# Motor_Driver.net
KiCad netlist of a schematic drawn in Altium Designer
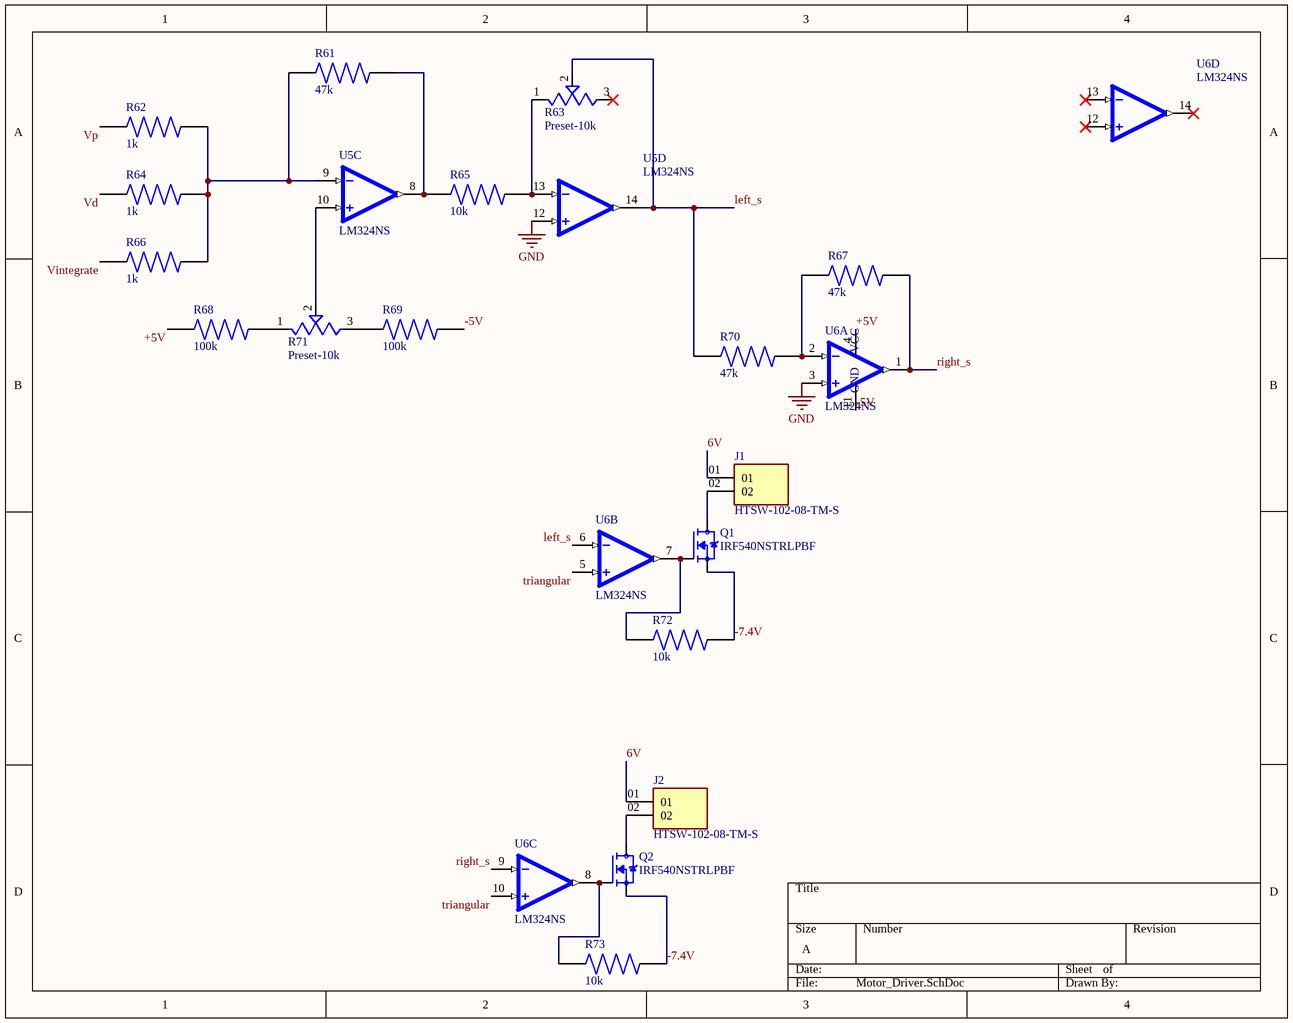
[diagram p0: Motor_Driver.SchDoc]

(export (version "E")
  (design (tool "Eeschema 10.0.6"))
  (components
    (comp (ref "J1")
      (value "HTSW-102-08-TM-S")
      (footprint "SAMTEC_HTSW-102-08-TM-S")
      (fields (field (name "MP") "HTSW10208TMS") (field (name "MF") "Samtec"))
      (libsource (lib "2 pin connector-2") (part "HTSW-102-08-TM-S"))
    )
    (comp (ref "J2")
      (value "HTSW-102-08-TM-S")
      (footprint "SAMTEC_HTSW-102-08-TM-S")
      (fields (field (name "MP") "HTSW10208TMS") (field (name "MF") "Samtec"))
      (libsource (lib "2 pin connector-2") (part "HTSW-102-08-TM-S"))
    )
    (comp (ref "Q1")
      (value "IRF540NSTRLPBF")
      (footprint "TRANS_IRF540NSTRLPBF")
      (fields (field (name "MF") "Infineon"))
      (libsource (lib "mosfet 2") (part "IRF540NSTRLPBF"))
    )
    (comp (ref "Q2")
      (value "IRF540NSTRLPBF")
      (footprint "TRANS_IRF540NSTRLPBF")
      (fields (field (name "MF") "Infineon"))
      (libsource (lib "mosfet 2") (part "IRF540NSTRLPBF"))
    )
    (comp (ref "R61")
      (value "47k")
      (footprint "RESC2012X60N")
      (fields (field (name "MF") "Yageo") (field (name "MP") "RC0805FR-0747KL"))
      (libsource (lib "47ks") (part "47k"))
    )
    (comp (ref "R62")
      (value "1k")
      (footprint "RESC2012X60N")
      (fields
        (field (name "DIGIKEY_PART_NUMBER") "311-1.00KCRTR-ND")
        (field (name "MF") "Yageo")
        (field (name "MP") "RC0805FR-071KL")
      )
      (libsource (lib "1ks") (part "1k"))
    )
    (comp (ref "R63")
      (value "Preset-10k")
      (footprint "TRIM_3306F-1-103")
      (description "TRIMMER - 6MM ROUND, SINGLE-TURN,CERMET, 10K OHMS ¦ Bourns 3306F-1-103")
      (fields (field (name "MF") "Bourns") (field (name "MP") "3306F-1-103"))
      (libsource (lib "3306F-1-103") (part "Preset"))
    )
    (comp (ref "R64")
      (value "1k")
      (footprint "RESC2012X60N")
      (fields
        (field (name "DIGIKEY_PART_NUMBER") "311-1.00KCRTR-ND")
        (field (name "MF") "Yageo")
        (field (name "MP") "RC0805FR-071KL")
      )
      (libsource (lib "1ks") (part "1k"))
    )
    (comp (ref "R65")
      (value "10k")
      (footprint "RESC2012X60N")
      (fields (field (name "MF") "Yageo") (field (name "MP") "RC0805FR-0710KL"))
      (libsource (lib "10ks") (part "10k"))
    )
    (comp (ref "R66")
      (value "1k")
      (footprint "RESC2012X60N")
      (fields
        (field (name "DIGIKEY_PART_NUMBER") "311-1.00KCRTR-ND")
        (field (name "MF") "Yageo")
        (field (name "MP") "RC0805FR-071KL")
      )
      (libsource (lib "1ks") (part "1k"))
    )
    (comp (ref "R67")
      (value "47k")
      (footprint "RESC2012X60N")
      (fields (field (name "MF") "Yageo") (field (name "MP") "RC0805FR-0747KL"))
      (libsource (lib "47ks") (part "47k"))
    )
    (comp (ref "R68")
      (value "100k")
      (footprint "RESC2012X60N")
      (fields (field (name "MF") "Yageo") (field (name "MP") "RC0805FR-07100KL"))
      (libsource (lib "100ks") (part "100k"))
    )
    (comp (ref "R69")
      (value "100k")
      (footprint "RESC2012X60N")
      (fields (field (name "MF") "Yageo") (field (name "MP") "RC0805FR-07100KL"))
      (libsource (lib "100ks") (part "100k"))
    )
    (comp (ref "R70")
      (value "47k")
      (footprint "RESC2012X60N")
      (fields (field (name "MF") "Yageo") (field (name "MP") "RC0805FR-0747KL"))
      (libsource (lib "47ks") (part "47k"))
    )
    (comp (ref "R71")
      (value "Preset-10k")
      (footprint "TRIM_3306F-1-103")
      (description "TRIMMER - 6MM ROUND, SINGLE-TURN,CERMET, 10K OHMS ¦ Bourns 3306F-1-103")
      (fields (field (name "MF") "Bourns") (field (name "MP") "3306F-1-103"))
      (libsource (lib "3306F-1-103") (part "Preset"))
    )
    (comp (ref "R72")
      (value "10k")
      (footprint "RESC2012X60N")
      (fields (field (name "MF") "Yageo") (field (name "MP") "RC0805FR-0710KL"))
      (libsource (lib "10ks") (part "10k"))
    )
    (comp (ref "R73")
      (value "10k")
      (footprint "RESC2012X60N")
      (fields (field (name "MF") "Yageo") (field (name "MP") "RC0805FR-0710KL"))
      (libsource (lib "10ks") (part "10k"))
    )
    (comp (ref "U5")
      (value "LM324NS")
      (footprint "SOIC127P780X200-14N")
      (description "4-Channel industry standard operational amplifier 14-SO 0 to 70; LM324NSRG4")
      (fields (field (name "MP") "LM324NSRG4") (field (name "MF") "Texas Instruments"))
      (libsource (lib "LM324NSRG4") (part "LM324NS"))
    )
    (comp (ref "U6")
      (value "LM324NS")
      (footprint "SOIC127P780X200-14N")
      (description "4-Channel industry standard operational amplifier 14-SO 0 to 70; LM324NSRG4")
      (fields (field (name "MP") "LM324NSRG4") (field (name "MF") "Texas Instruments"))
      (libsource (lib "LM324NSRG4") (part "LM324NS"))
    )
  )
  (nets
    (net (code "1") (name "/+5V") (class "Default")
      (node (ref "R68") (pin "1") (pinfunction "1_1") (pintype "passive"))
      (node (ref "U6") (pin "4") (pinfunction "VCC_4") (pintype "power_in"))
    )
    (net (code "2") (name "/-5V") (class "Default")
      (node (ref "R69") (pin "2") (pinfunction "2_2") (pintype "passive"))
      (node (ref "U6") (pin "11") (pinfunction "GND_11") (pintype "power_in"))
    )
    (net (code "3") (name "/-7.4V") (class "Default")
      (node (ref "Q1") (pin "3") (pinfunction "S_3") (pintype "passive"))
      (node (ref "Q2") (pin "3") (pinfunction "S_3") (pintype "passive"))
      (node (ref "R72") (pin "2") (pinfunction "2_2") (pintype "passive"))
      (node (ref "R73") (pin "2") (pinfunction "2_2") (pintype "passive"))
    )
    (net (code "4") (name "/6V") (class "Default")
      (node (ref "J1") (pin "01") (pinfunction "01_01") (pintype "passive"))
      (node (ref "J2") (pin "01") (pinfunction "01_01") (pintype "passive"))
    )
    (net (code "5") (name "/Vd") (class "Default")
      (node (ref "R64") (pin "1") (pinfunction "1_1") (pintype "passive"))
    )
    (net (code "6") (name "/Vintegrate") (class "Default")
      (node (ref "R66") (pin "1") (pinfunction "1_1") (pintype "passive"))
    )
    (net (code "7") (name "/Vp") (class "Default")
      (node (ref "R62") (pin "1") (pinfunction "1_1") (pintype "passive"))
    )
    (net (code "8") (name "/left_s") (class "Default")
      (node (ref "R63") (pin "2") (pinfunction "W_2") (pintype "passive"))
      (node (ref "R70") (pin "1") (pinfunction "1_1") (pintype "passive"))
      (node (ref "U5") (pin "14") (pinfunction "4OUT_14") (pintype "output"))
      (node (ref "U6") (pin "6") (pinfunction "2IN-_6") (pintype "input"))
    )
    (net (code "9") (name "/right_s") (class "Default")
      (node (ref "R67") (pin "2") (pinfunction "2_2") (pintype "passive"))
      (node (ref "U6") (pin "1") (pinfunction "1OUT_1") (pintype "output"))
      (node (ref "U6") (pin "9") (pinfunction "3IN-_9") (pintype "input"))
    )
    (net (code "10") (name "/triangular") (class "Default")
      (node (ref "U6") (pin "10") (pinfunction "3IN+_10") (pintype "input"))
      (node (ref "U6") (pin "5") (pinfunction "2IN+_5") (pintype "input"))
    )
    (net (code "11") (name "GND") (class "Default")
      (node (ref "U5") (pin "12") (pinfunction "4IN+_12") (pintype "input"))
      (node (ref "U6") (pin "3") (pinfunction "1IN+_3") (pintype "input"))
    )
    (net (code "12") (name "Net-(Q1-D)") (class "Default")
      (node (ref "J1") (pin "02") (pinfunction "02_02") (pintype "passive"))
      (node (ref "Q1") (pin "2") (pinfunction "D_2") (pintype "passive"))
    )
    (net (code "13") (name "Net-(Q1-G)") (class "Default")
      (node (ref "Q1") (pin "1") (pinfunction "G_1") (pintype "passive"))
      (node (ref "R72") (pin "1") (pinfunction "1_1") (pintype "passive"))
      (node (ref "U6") (pin "7") (pinfunction "2OUT_7") (pintype "output"))
    )
    (net (code "14") (name "Net-(Q2-D)") (class "Default")
      (node (ref "J2") (pin "02") (pinfunction "02_02") (pintype "passive"))
      (node (ref "Q2") (pin "2") (pinfunction "D_2") (pintype "passive"))
    )
    (net (code "15") (name "Net-(Q2-G)") (class "Default")
      (node (ref "Q2") (pin "1") (pinfunction "G_1") (pintype "passive"))
      (node (ref "R73") (pin "1") (pinfunction "1_1") (pintype "passive"))
      (node (ref "U6") (pin "8") (pinfunction "3OUT_8") (pintype "output"))
    )
    (net (code "16") (name "Net-(R63-CCW)") (class "Default")
      (node (ref "R63") (pin "1") (pinfunction "CCW_1") (pintype "passive"))
      (node (ref "R65") (pin "2") (pinfunction "2_2") (pintype "passive"))
      (node (ref "U5") (pin "13") (pinfunction "4IN-_13") (pintype "input"))
    )
    (net (code "17") (name "Net-(R71-CCW)") (class "Default")
      (node (ref "R68") (pin "2") (pinfunction "2_2") (pintype "passive"))
      (node (ref "R71") (pin "1") (pinfunction "CCW_1") (pintype "passive"))
    )
    (net (code "18") (name "Net-(R71-CW)") (class "Default")
      (node (ref "R69") (pin "1") (pinfunction "1_1") (pintype "passive"))
      (node (ref "R71") (pin "3") (pinfunction "CW_3") (pintype "passive"))
    )
    (net (code "19") (name "Net-(R71-W)") (class "Default")
      (node (ref "R71") (pin "2") (pinfunction "W_2") (pintype "passive"))
      (node (ref "U5") (pin "10") (pinfunction "3IN+_10") (pintype "input"))
    )
    (net (code "20") (name "Net-(U5C-3IN-)") (class "Default")
      (node (ref "R61") (pin "1") (pinfunction "1_1") (pintype "passive"))
      (node (ref "R62") (pin "2") (pinfunction "2_2") (pintype "passive"))
      (node (ref "R64") (pin "2") (pinfunction "2_2") (pintype "passive"))
      (node (ref "R66") (pin "2") (pinfunction "2_2") (pintype "passive"))
      (node (ref "U5") (pin "9") (pinfunction "3IN-_9") (pintype "input"))
    )
    (net (code "21") (name "Net-(U5C-3OUT)") (class "Default")
      (node (ref "R61") (pin "2") (pinfunction "2_2") (pintype "passive"))
      (node (ref "R65") (pin "1") (pinfunction "1_1") (pintype "passive"))
      (node (ref "U5") (pin "8") (pinfunction "3OUT_8") (pintype "output"))
    )
    (net (code "22") (name "Net-(U6A-1IN-)") (class "Default")
      (node (ref "R67") (pin "1") (pinfunction "1_1") (pintype "passive"))
      (node (ref "R70") (pin "2") (pinfunction "2_2") (pintype "passive"))
      (node (ref "U6") (pin "2") (pinfunction "1IN-_2") (pintype "input"))
    )
    (net (code "23") (name "unconnected-(R63-CW-Pad3)") (class "Default")
      (node (ref "R63") (pin "3") (pinfunction "CW_3") (pintype "passive+no_connect"))
    )
    (net (code "24") (name "unconnected-(U6D-4IN+-Pad12)") (class "Default")
      (node (ref "U6") (pin "12") (pinfunction "4IN+_12") (pintype "input+no_connect"))
    )
    (net (code "25") (name "unconnected-(U6D-4IN--Pad13)") (class "Default")
      (node (ref "U6") (pin "13") (pinfunction "4IN-_13") (pintype "input+no_connect"))
    )
    (net (code "26") (name "unconnected-(U6D-4OUT-Pad14)") (class "Default")
      (node (ref "U6") (pin "14") (pinfunction "4OUT_14") (pintype "output+no_connect"))
    )
  )
)
